# ControllableClock.net
KiCad netlist of a schematic drawn in Altium Designer
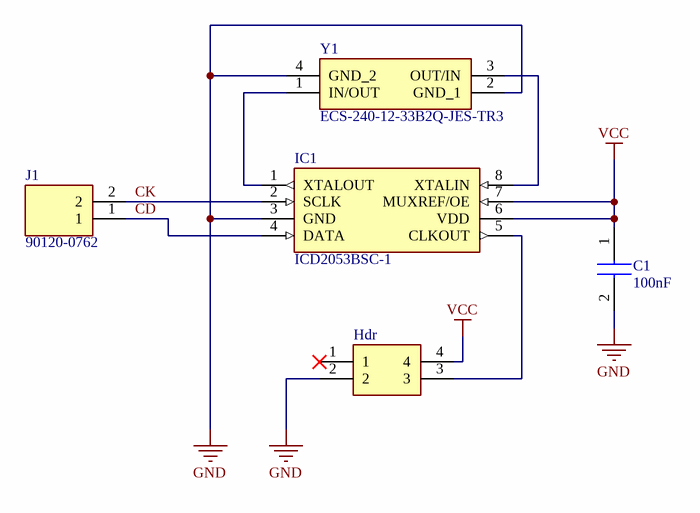
[diagram p0: ControllableClock.SchDoc]

(export (version "E")
  (design (tool "Eeschema 10.0.6"))
  (components
    (comp (ref "C1")
      (value "100nF")
      (footprint "SamacSys:CAPC2012X145N")
      (description "Capacitor")
      (fields
        (field (name "MANUFACTURER_PART_NUMBER") "C2012X7R1H104K125AM")
        (field (name "MOUSER PART NUMBER") "810-C2012X7R1H104KT5")
      )
      (libsource (lib "*") (part "C2012X7R1H104K125AM"))
    )
    (comp (ref "Hdr")
      (value "~")
      (footprint "SamacSys:DIPS762W56P1524L1778H241Q4N")
      (description "Header only")
      (fields
        (field (name "MANUFACTURER_PART_NUMBER") "1107741")
        (field (name "MOUSER PART NUMBER") "535-1107741")
      )
      (libsource (lib "*") (part "1107741"))
    )
    (comp (ref "IC1")
      (value "ICD2053BSC-1")
      (footprint "SamacSys:SOIC127P602X173-8N")
      (description "Integrated Circuit")
      (libsource (lib "*") (part "ICD2053BSC-1"))
    )
    (comp (ref "J1")
      (value "90120-0762")
      (footprint "SamacSys:HDRV2W35P0X254_1X2_508X249X560P")
      (description "Connector")
      (fields (field (name "MOUSER PART NUMBER") "538-90120-0762"))
      (libsource (lib "SamacSys") (part "90120-0762"))
    )
    (comp (ref "Y1")
      (value "ECS-240-12-33B2Q-JES-TR3")
      (footprint "SamacSys:ECS2401233B2QJESTR3")
      (description "Crystal or Oscillator")
      (libsource (lib "*") (part "ECS-240-12-33B2Q-JES-TR3"))
    )
  )
  (nets
    (net (code "1") (name "/CD") (class "Default")
      (node (ref "IC1") (pin "4") (pinfunction "DATA_4") (pintype "input"))
      (node (ref "J1") (pin "1") (pinfunction "1_1") (pintype "passive"))
    )
    (net (code "2") (name "/CK") (class "Default")
      (node (ref "IC1") (pin "2") (pinfunction "SCLK_2") (pintype "input"))
      (node (ref "J1") (pin "2") (pinfunction "2_2") (pintype "passive"))
    )
    (net (code "3") (name "GND") (class "Default")
      (node (ref "C1") (pin "2") (pinfunction "2_2") (pintype "passive"))
      (node (ref "Hdr") (pin "2") (pinfunction "2_2") (pintype "passive"))
      (node (ref "IC1") (pin "3") (pinfunction "GND_3") (pintype "power_in"))
      (node (ref "Y1") (pin "2") (pinfunction "GND_1_2") (pintype "passive"))
      (node (ref "Y1") (pin "4") (pinfunction "GND_2_4") (pintype "passive"))
    )
    (net (code "4") (name "Net-(IC1-CLKOUT)") (class "Default")
      (node (ref "Hdr") (pin "3") (pinfunction "3_3") (pintype "passive"))
      (node (ref "IC1") (pin "5") (pinfunction "CLKOUT_5") (pintype "output"))
    )
    (net (code "5") (name "Net-(IC1-XTALIN)") (class "Default")
      (node (ref "IC1") (pin "8") (pinfunction "XTALIN_8") (pintype "input"))
      (node (ref "Y1") (pin "3") (pinfunction "OUT/IN_3") (pintype "passive"))
    )
    (net (code "6") (name "Net-(IC1-XTALOUT)") (class "Default")
      (node (ref "IC1") (pin "1") (pinfunction "XTALOUT_1") (pintype "output"))
      (node (ref "Y1") (pin "1") (pinfunction "IN/OUT_1") (pintype "passive"))
    )
    (net (code "7") (name "VCC") (class "Default")
      (node (ref "C1") (pin "1") (pinfunction "1_1") (pintype "passive"))
      (node (ref "Hdr") (pin "4") (pinfunction "4_4") (pintype "passive"))
      (node (ref "IC1") (pin "6") (pinfunction "VDD_6") (pintype "power_in"))
      (node (ref "IC1") (pin "7") (pinfunction "MUXREF/OE_7") (pintype "input"))
    )
    (net (code "8") (name "unconnected-(Hdr-Pad1)") (class "Default")
      (node (ref "Hdr") (pin "1") (pinfunction "1_1") (pintype "passive+no_connect"))
    )
  )
)
